# tempLogger.net
KiCad netlist of a schematic drawn in EAGLE
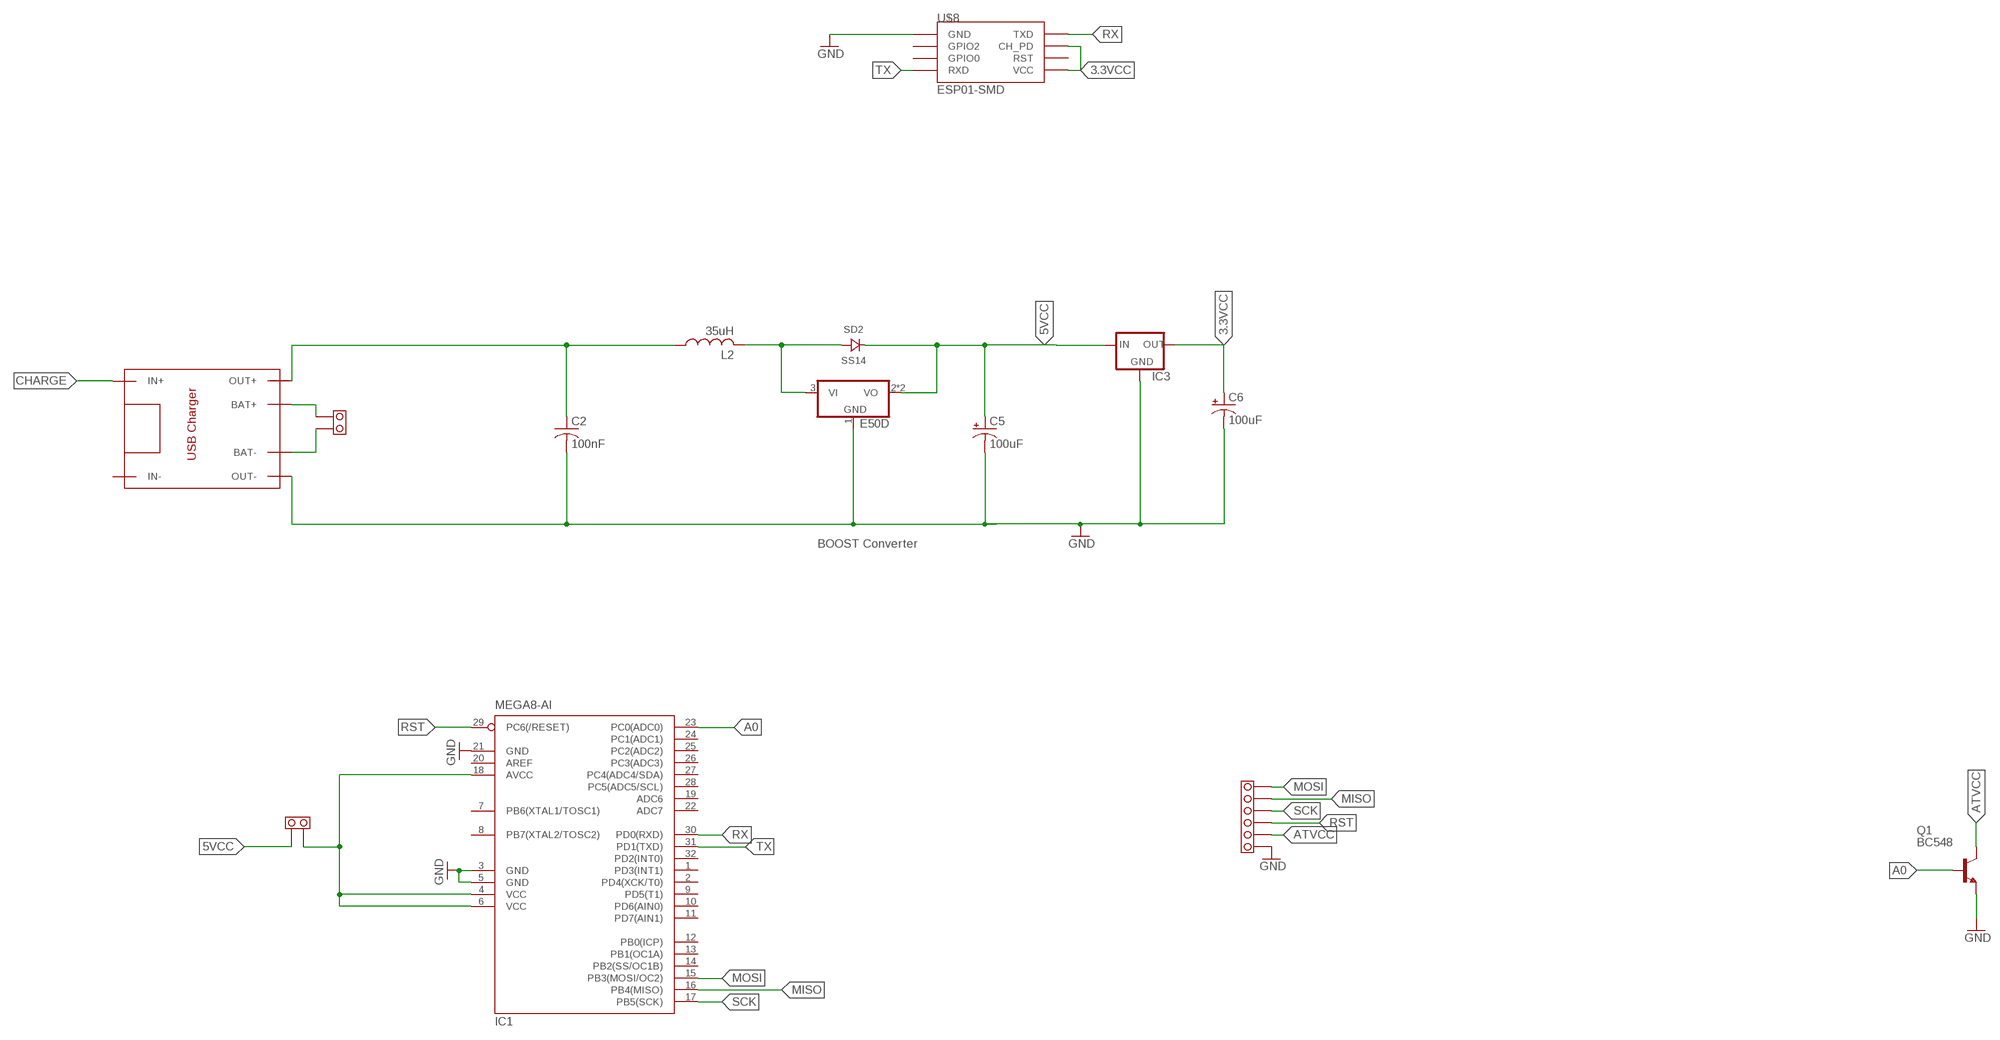
[diagram p0: schematic, sheet 1]

(export (version "E")
  (design (tool "Eeschema 10.0.6"))
  (components
    (comp (ref "C2")
      (value "100nF")
      (footprint "eagle-import:C1206")
      (libsource (lib "eagle-import") (part "C-USC1206"))
    )
    (comp (ref "C5")
      (value "100uF")
      (footprint "eagle-import:150CLZ-0810")
      (libsource (lib "eagle-import") (part "CPOL-US150CLZ-0810"))
    )
    (comp (ref "C6")
      (value "100uF")
      (footprint "eagle-import:153CLV-0405")
      (libsource (lib "eagle-import") (part "CPOL-US153CLV-0405"))
    )
    (comp (ref "IC1")
      (value "MEGA8-AI")
      (footprint "eagle-import:TQFP32-08")
      (fields (field (name "MPN") "ATMEGA8-16AU"))
      (libsource (lib "eagle-import") (part "MEGA8-AI"))
    )
    (comp (ref "IC2")
      (value "E50D")
      (footprint "eagle-import:SOT89")
      (libsource (lib "eagle-import") (part "E50D"))
    )
    (comp (ref "IC3")
      (value "LM1117")
      (footprint "eagle-import:SOT223")
      (libsource (lib "eagle-import") (part "LM1117"))
    )
    (comp (ref "L2")
      (value "35uH")
      (footprint "eagle-import:PIS2816")
      (libsource (lib "eagle-import") (part "L-USPIS2816"))
    )
    (comp (ref "Q1")
      (value "BC548")
      (footprint "eagle-import:TO92-EBC")
      (libsource (lib "eagle-import") (part "BC548"))
    )
    (comp (ref "SD2")
      (value "SS14")
      (footprint "eagle-import:DO214")
      (libsource (lib "eagle-import") (part "SS14"))
    )
    (comp (ref "U$1")
      (value "BERG_2")
      (footprint "eagle-import:BERG_2")
      (libsource (lib "eagle-import") (part "BERG_2"))
    )
    (comp (ref "U$2")
      (value "TP4056")
      (footprint "eagle-import:TP4056")
      (libsource (lib "eagle-import") (part "TP4056"))
    )
    (comp (ref "U$3")
      (value "BERG_6")
      (footprint "eagle-import:BERG_6")
      (libsource (lib "eagle-import") (part "BERG_6"))
    )
    (comp (ref "U$4")
      (value "BERG_2")
      (footprint "eagle-import:BERG_2")
      (libsource (lib "eagle-import") (part "BERG_2"))
    )
    (comp (ref "U$8")
      (value "ESP01-SMD")
      (footprint "eagle-import:ESP01_SMD")
      (libsource (lib "eagle-import") (part "ESP01-SMD"))
    )
  )
  (nets
    (net (code "1") (name "3.3VCC") (class "Default")
      (node (ref "C6") (pin "+") (pinfunction "+_+") (pintype "passive"))
      (node (ref "IC3") (pin "2") (pinfunction "OUT_2") (pintype "passive"))
      (node (ref "U$8") (pin "CH_PD") (pinfunction "CH_PD_CH_PD") (pintype "bidirectional"))
      (node (ref "U$8") (pin "VCC") (pinfunction "VCC_VCC") (pintype "bidirectional"))
    )
    (net (code "2") (name "5VCC") (class "Default")
      (node (ref "C5") (pin "+") (pinfunction "+_+") (pintype "passive"))
      (node (ref "IC2") (pin "2") (pinfunction "VO_2") (pintype "passive"))
      (node (ref "IC2") (pin "2@1") (pinfunction "VO_2@1") (pintype "passive"))
      (node (ref "IC3") (pin "3") (pinfunction "IN_3") (pintype "input"))
      (node (ref "SD2") (pin "CATHODE") (pinfunction "CATHODE_CATHODE") (pintype "bidirectional"))
      (node (ref "U$1") (pin "F") (pinfunction "P$2_F") (pintype "bidirectional"))
    )
    (net (code "3") (name "A0") (class "Default")
      (node (ref "IC1") (pin "23") (pinfunction "PC0(ADC0)_23") (pintype "bidirectional"))
      (node (ref "Q1") (pin "B") (pinfunction "B_B") (pintype "passive"))
    )
    (net (code "4") (name "ATVCC") (class "Default")
      (node (ref "IC1") (pin "18") (pinfunction "AVCC_18") (pintype "power_in"))
      (node (ref "IC1") (pin "4") (pinfunction "VCC_4") (pintype "power_in"))
      (node (ref "IC1") (pin "6") (pinfunction "VCC_6") (pintype "power_in"))
      (node (ref "Q1") (pin "C") (pinfunction "C_C") (pintype "passive"))
      (node (ref "U$1") (pin "E") (pinfunction "P$1_E") (pintype "bidirectional"))
      (node (ref "U$3") (pin "I") (pinfunction "P$5_I") (pintype "bidirectional"))
    )
    (net (code "5") (name "CHARGE") (class "Default")
      (node (ref "U$2") (pin "IN+") (pinfunction "IN+_IN+") (pintype "bidirectional"))
    )
    (net (code "6") (name "GND") (class "Default")
      (node (ref "C2") (pin "2") (pinfunction "2_2") (pintype "passive"))
      (node (ref "C5") (pin "-") (pinfunction "-_-") (pintype "passive"))
      (node (ref "C6") (pin "-") (pinfunction "-_-") (pintype "passive"))
      (node (ref "IC1") (pin "21") (pinfunction "GND_21") (pintype "power_in"))
      (node (ref "IC1") (pin "3") (pinfunction "GND_3") (pintype "power_in"))
      (node (ref "IC1") (pin "5") (pinfunction "GND_5") (pintype "power_in"))
      (node (ref "IC2") (pin "1") (pinfunction "GND_1") (pintype "passive"))
      (node (ref "IC3") (pin "1") (pinfunction "GND_1") (pintype "input"))
      (node (ref "Q1") (pin "E") (pinfunction "E_E") (pintype "passive"))
      (node (ref "U$2") (pin "OUT-") (pinfunction "OUT-_OUT-") (pintype "bidirectional"))
      (node (ref "U$3") (pin "J") (pinfunction "P$6_J") (pintype "bidirectional"))
      (node (ref "U$8") (pin "GND") (pinfunction "GND_GND") (pintype "bidirectional"))
    )
    (net (code "7") (name "MISO") (class "Default")
      (node (ref "IC1") (pin "16") (pinfunction "PB4(MISO)_16") (pintype "bidirectional"))
      (node (ref "U$3") (pin "F") (pinfunction "P$2_F") (pintype "bidirectional"))
    )
    (net (code "8") (name "MOSI") (class "Default")
      (node (ref "IC1") (pin "15") (pinfunction "PB3(MOSI/OC2)_15") (pintype "bidirectional"))
      (node (ref "U$3") (pin "E") (pinfunction "P$1_E") (pintype "bidirectional"))
    )
    (net (code "9") (name "Net-(C2-Pad1)") (class "Default")
      (node (ref "C2") (pin "1") (pinfunction "1_1") (pintype "passive"))
      (node (ref "L2") (pin "1") (pinfunction "1_1") (pintype "passive"))
      (node (ref "U$2") (pin "OUT+") (pinfunction "OUT+_OUT+") (pintype "bidirectional"))
    )
    (net (code "10") (name "Net-(IC2-VI)") (class "Default")
      (node (ref "IC2") (pin "3") (pinfunction "VI_3") (pintype "input"))
      (node (ref "L2") (pin "2") (pinfunction "2_2") (pintype "passive"))
      (node (ref "SD2") (pin "ANODE") (pinfunction "ANODE_ANODE") (pintype "bidirectional"))
    )
    (net (code "11") (name "Net-(U$4-P$1)") (class "Default")
      (node (ref "U$2") (pin "BAT-") (pinfunction "BAT-_BAT-") (pintype "bidirectional"))
      (node (ref "U$4") (pin "E") (pinfunction "P$1_E") (pintype "bidirectional"))
    )
    (net (code "12") (name "Net-(U$4-P$2)") (class "Default")
      (node (ref "U$2") (pin "BAT+") (pinfunction "BAT+_BAT+") (pintype "bidirectional"))
      (node (ref "U$4") (pin "F") (pinfunction "P$2_F") (pintype "bidirectional"))
    )
    (net (code "13") (name "RST") (class "Default")
      (node (ref "IC1") (pin "29") (pinfunction "PC6(/RESET)_29") (pintype "bidirectional"))
      (node (ref "U$3") (pin "H") (pinfunction "P$4_H") (pintype "bidirectional"))
    )
    (net (code "14") (name "RX") (class "Default")
      (node (ref "IC1") (pin "30") (pinfunction "PD0(RXD)_30") (pintype "bidirectional"))
      (node (ref "U$8") (pin "TX") (pinfunction "TXD_TX") (pintype "bidirectional"))
    )
    (net (code "15") (name "SCK") (class "Default")
      (node (ref "IC1") (pin "17") (pinfunction "PB5(SCK)_17") (pintype "bidirectional"))
      (node (ref "U$3") (pin "G") (pinfunction "P$3_G") (pintype "bidirectional"))
    )
    (net (code "16") (name "TX") (class "Default")
      (node (ref "IC1") (pin "31") (pinfunction "PD1(TXD)_31") (pintype "bidirectional"))
      (node (ref "U$8") (pin "RX") (pinfunction "RXD_RX") (pintype "bidirectional"))
    )
    (net (code "17") (name "unconnected-(IC1-ADC6-Pad19)") (class "Default")
      (node (ref "IC1") (pin "19") (pinfunction "ADC6_19") (pintype "bidirectional"))
    )
    (net (code "18") (name "unconnected-(IC1-ADC7-Pad22)") (class "Default")
      (node (ref "IC1") (pin "22") (pinfunction "ADC7_22") (pintype "bidirectional"))
    )
    (net (code "19") (name "unconnected-(IC1-AREF-Pad20)") (class "Default")
      (node (ref "IC1") (pin "20") (pinfunction "AREF_20") (pintype "passive"))
    )
    (net (code "20") (name "unconnected-(IC1-PB0(ICP)-Pad12)") (class "Default")
      (node (ref "IC1") (pin "12") (pinfunction "PB0(ICP)_12") (pintype "bidirectional"))
    )
    (net (code "21") (name "unconnected-(IC1-PB1(OC1A)-Pad13)") (class "Default")
      (node (ref "IC1") (pin "13") (pinfunction "PB1(OC1A)_13") (pintype "bidirectional"))
    )
    (net (code "22") (name "unconnected-(IC1-PB2(SS{slash}OC1B)-Pad14)") (class "Default")
      (node (ref "IC1") (pin "14") (pinfunction "PB2(SS/OC1B)_14") (pintype "bidirectional"))
    )
    (net (code "23") (name "unconnected-(IC1-PB6(XTAL1{slash}TOSC1)-Pad7)") (class "Default")
      (node (ref "IC1") (pin "7") (pinfunction "PB6(XTAL1/TOSC1)_7") (pintype "bidirectional"))
    )
    (net (code "24") (name "unconnected-(IC1-PB7(XTAL2{slash}TOSC2)-Pad8)") (class "Default")
      (node (ref "IC1") (pin "8") (pinfunction "PB7(XTAL2/TOSC2)_8") (pintype "bidirectional"))
    )
    (net (code "25") (name "unconnected-(IC1-PC1(ADC1)-Pad24)") (class "Default")
      (node (ref "IC1") (pin "24") (pinfunction "PC1(ADC1)_24") (pintype "bidirectional"))
    )
    (net (code "26") (name "unconnected-(IC1-PC2(ADC2)-Pad25)") (class "Default")
      (node (ref "IC1") (pin "25") (pinfunction "PC2(ADC2)_25") (pintype "bidirectional"))
    )
    (net (code "27") (name "unconnected-(IC1-PC3(ADC3)-Pad26)") (class "Default")
      (node (ref "IC1") (pin "26") (pinfunction "PC3(ADC3)_26") (pintype "bidirectional"))
    )
    (net (code "28") (name "unconnected-(IC1-PC4(ADC4{slash}SDA)-Pad27)") (class "Default")
      (node (ref "IC1") (pin "27") (pinfunction "PC4(ADC4/SDA)_27") (pintype "bidirectional"))
    )
    (net (code "29") (name "unconnected-(IC1-PC5(ADC5{slash}SCL)-Pad28)") (class "Default")
      (node (ref "IC1") (pin "28") (pinfunction "PC5(ADC5/SCL)_28") (pintype "bidirectional"))
    )
    (net (code "30") (name "unconnected-(IC1-PD2(INT0)-Pad32)") (class "Default")
      (node (ref "IC1") (pin "32") (pinfunction "PD2(INT0)_32") (pintype "bidirectional"))
    )
    (net (code "31") (name "unconnected-(IC1-PD3(INT1)-Pad1)") (class "Default")
      (node (ref "IC1") (pin "1") (pinfunction "PD3(INT1)_1") (pintype "bidirectional"))
    )
    (net (code "32") (name "unconnected-(IC1-PD4(XCK{slash}T0)-Pad2)") (class "Default")
      (node (ref "IC1") (pin "2") (pinfunction "PD4(XCK/T0)_2") (pintype "bidirectional"))
    )
    (net (code "33") (name "unconnected-(IC1-PD5(T1)-Pad9)") (class "Default")
      (node (ref "IC1") (pin "9") (pinfunction "PD5(T1)_9") (pintype "bidirectional"))
    )
    (net (code "34") (name "unconnected-(IC1-PD6(AIN0)-Pad10)") (class "Default")
      (node (ref "IC1") (pin "10") (pinfunction "PD6(AIN0)_10") (pintype "bidirectional"))
    )
    (net (code "35") (name "unconnected-(IC1-PD7(AIN1)-Pad11)") (class "Default")
      (node (ref "IC1") (pin "11") (pinfunction "PD7(AIN1)_11") (pintype "bidirectional"))
    )
    (net (code "36") (name "unconnected-(U$2-PadIN-)") (class "Default")
      (node (ref "U$2") (pin "IN-") (pinfunction "IN-_IN-") (pintype "bidirectional"))
    )
    (net (code "37") (name "unconnected-(U$8-PadGPIO0)") (class "Default")
      (node (ref "U$8") (pin "GPIO0") (pinfunction "GPIO0_GPIO0") (pintype "bidirectional"))
    )
    (net (code "38") (name "unconnected-(U$8-PadGPIO2)") (class "Default")
      (node (ref "U$8") (pin "GPIO2") (pinfunction "GPIO2_GPIO2") (pintype "bidirectional"))
    )
    (net (code "39") (name "unconnected-(U$8-PadRST)") (class "Default")
      (node (ref "U$8") (pin "RST") (pinfunction "RST_RST") (pintype "bidirectional"))
    )
  )
)
